# PentaBlinkyCR2032.net
KiCad netlist of a schematic drawn in EAGLE
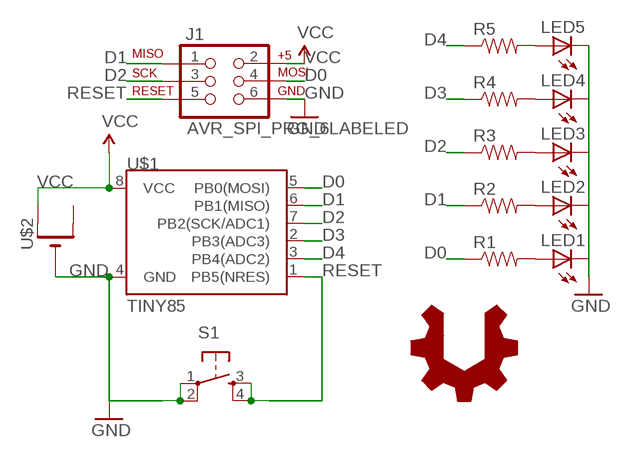
[diagram p0: schematic, sheet 1]

(export (version "E")
  (design (tool "Eeschema 10.0.6"))
  (components
    (comp (ref "J1")
      (value "AVR_SPI_PRG_6LABELED")
      (footprint "eagle-import:2X3-NS")
      (libsource (lib "eagle-import") (part "AVR_SPI_PRG_6LABELED"))
    )
    (comp (ref "LED1")
      (value "LED5MM")
      (footprint "eagle-import:LED5MM")
      (libsource (lib "eagle-import") (part "LED5MM"))
    )
    (comp (ref "LED2")
      (value "LED5MM")
      (footprint "eagle-import:LED5MM")
      (libsource (lib "eagle-import") (part "LED5MM"))
    )
    (comp (ref "LED3")
      (value "LED5MM")
      (footprint "eagle-import:LED5MM")
      (libsource (lib "eagle-import") (part "LED5MM"))
    )
    (comp (ref "LED4")
      (value "LED5MM")
      (footprint "eagle-import:LED5MM")
      (libsource (lib "eagle-import") (part "LED5MM"))
    )
    (comp (ref "LED5")
      (value "LED5MM")
      (footprint "eagle-import:LED5MM")
      (libsource (lib "eagle-import") (part "LED5MM"))
    )
    (comp (ref "R1")
      (value "RESISTORAXIAL-0.3")
      (footprint "eagle-import:AXIAL-0.3")
      (libsource (lib "eagle-import") (part "RESISTORAXIAL-0.3"))
    )
    (comp (ref "R2")
      (value "RESISTORAXIAL-0.3")
      (footprint "eagle-import:AXIAL-0.3")
      (libsource (lib "eagle-import") (part "RESISTORAXIAL-0.3"))
    )
    (comp (ref "R3")
      (value "RESISTORAXIAL-0.3")
      (footprint "eagle-import:AXIAL-0.3")
      (libsource (lib "eagle-import") (part "RESISTORAXIAL-0.3"))
    )
    (comp (ref "R4")
      (value "RESISTORAXIAL-0.3")
      (footprint "eagle-import:AXIAL-0.3")
      (libsource (lib "eagle-import") (part "RESISTORAXIAL-0.3"))
    )
    (comp (ref "R5")
      (value "RESISTORAXIAL-0.3")
      (footprint "eagle-import:AXIAL-0.3")
      (libsource (lib "eagle-import") (part "RESISTORAXIAL-0.3"))
    )
    (comp (ref "S1")
      (value "TAC_SWITCHPTH")
      (footprint "eagle-import:TACTILE-PTH")
      (libsource (lib "eagle-import") (part "TAC_SWITCHPTH"))
    )
    (comp (ref "U$1")
      (value "TINY85")
      (footprint "eagle-import:DIP08")
      (libsource (lib "eagle-import") (part "ATTINY13DIP"))
    )
    (comp (ref "U$2")
      (value "CR2032THM")
      (footprint "eagle-import:CR2032-THRU")
      (libsource (lib "eagle-import") (part "CR2032THM"))
    )
    (comp (ref "U$3")
      (value "USER_HACKABLE")
      (footprint "eagle-import:USER_HACKABLE")
      (libsource (lib "eagle-import") (part "USER_HACKABLE"))
    )
  )
  (nets
    (net (code "1") (name "/D0") (class "Default")
      (node (ref "J1") (pin "4") (pinfunction "MOSI_4") (pintype "passive"))
      (node (ref "R1") (pin "P$1") (pinfunction "1_P$1") (pintype "passive"))
      (node (ref "U$1") (pin "5") (pinfunction "PB0(MOSI)_5") (pintype "bidirectional"))
    )
    (net (code "2") (name "/D1") (class "Default")
      (node (ref "J1") (pin "1") (pinfunction "MISO_1") (pintype "passive"))
      (node (ref "R2") (pin "P$1") (pinfunction "1_P$1") (pintype "passive"))
      (node (ref "U$1") (pin "6") (pinfunction "PB1(MISO)_6") (pintype "bidirectional"))
    )
    (net (code "3") (name "/D2") (class "Default")
      (node (ref "J1") (pin "3") (pinfunction "SCK_3") (pintype "passive"))
      (node (ref "R3") (pin "P$1") (pinfunction "1_P$1") (pintype "passive"))
      (node (ref "U$1") (pin "7") (pinfunction "PB2(SCK/ADC1)_7") (pintype "bidirectional"))
    )
    (net (code "4") (name "/D3") (class "Default")
      (node (ref "R4") (pin "P$1") (pinfunction "1_P$1") (pintype "passive"))
      (node (ref "U$1") (pin "2") (pinfunction "PB3(ADC3)_2") (pintype "bidirectional"))
    )
    (net (code "5") (name "/D4") (class "Default")
      (node (ref "R5") (pin "P$1") (pinfunction "1_P$1") (pintype "passive"))
      (node (ref "U$1") (pin "3") (pinfunction "PB4(ADC2)_3") (pintype "bidirectional"))
    )
    (net (code "6") (name "/RESET") (class "Default")
      (node (ref "J1") (pin "5") (pinfunction "RST_5") (pintype "passive"))
      (node (ref "S1") (pin "3") (pinfunction "3_3") (pintype "passive"))
      (node (ref "S1") (pin "4") (pinfunction "4_4") (pintype "passive"))
      (node (ref "U$1") (pin "1") (pinfunction "PB5(NRES)_1") (pintype "bidirectional"))
    )
    (net (code "7") (name "GND") (class "Default")
      (node (ref "J1") (pin "6") (pinfunction "GND_6") (pintype "passive"))
      (node (ref "LED1") (pin "K") (pinfunction "C_K") (pintype "passive"))
      (node (ref "LED2") (pin "K") (pinfunction "C_K") (pintype "passive"))
      (node (ref "LED3") (pin "K") (pinfunction "C_K") (pintype "passive"))
      (node (ref "LED4") (pin "K") (pinfunction "C_K") (pintype "passive"))
      (node (ref "LED5") (pin "K") (pinfunction "C_K") (pintype "passive"))
      (node (ref "S1") (pin "1") (pinfunction "1_1") (pintype "passive"))
      (node (ref "S1") (pin "2") (pinfunction "2_2") (pintype "passive"))
      (node (ref "U$1") (pin "4") (pinfunction "GND_4") (pintype "bidirectional"))
      (node (ref "U$2") (pin "-") (pinfunction "-_-") (pintype "passive"))
    )
    (net (code "8") (name "Net-(R1-2)") (class "Default")
      (node (ref "LED1") (pin "A") (pinfunction "A_A") (pintype "passive"))
      (node (ref "R1") (pin "P$2") (pinfunction "2_P$2") (pintype "passive"))
    )
    (net (code "9") (name "Net-(R2-2)") (class "Default")
      (node (ref "LED2") (pin "A") (pinfunction "A_A") (pintype "passive"))
      (node (ref "R2") (pin "P$2") (pinfunction "2_P$2") (pintype "passive"))
    )
    (net (code "10") (name "Net-(R3-2)") (class "Default")
      (node (ref "LED3") (pin "A") (pinfunction "A_A") (pintype "passive"))
      (node (ref "R3") (pin "P$2") (pinfunction "2_P$2") (pintype "passive"))
    )
    (net (code "11") (name "Net-(R4-2)") (class "Default")
      (node (ref "LED4") (pin "A") (pinfunction "A_A") (pintype "passive"))
      (node (ref "R4") (pin "P$2") (pinfunction "2_P$2") (pintype "passive"))
    )
    (net (code "12") (name "Net-(R5-2)") (class "Default")
      (node (ref "LED5") (pin "A") (pinfunction "A_A") (pintype "passive"))
      (node (ref "R5") (pin "P$2") (pinfunction "2_P$2") (pintype "passive"))
    )
    (net (code "13") (name "VCC") (class "Default")
      (node (ref "J1") (pin "2") (pinfunction "V+_2") (pintype "passive"))
      (node (ref "U$1") (pin "8") (pinfunction "VCC_8") (pintype "bidirectional"))
      (node (ref "U$2") (pin "+1") (pinfunction "+_+1") (pintype "passive"))
    )
    (net (code "14") (name "unconnected-(U$2-+1-Pad+2)") (class "Default")
      (node (ref "U$2") (pin "+2") (pinfunction "+1_+2") (pintype "passive"))
    )
  )
)
